# Main.net
KiCad netlist of a schematic drawn in Altium Designer
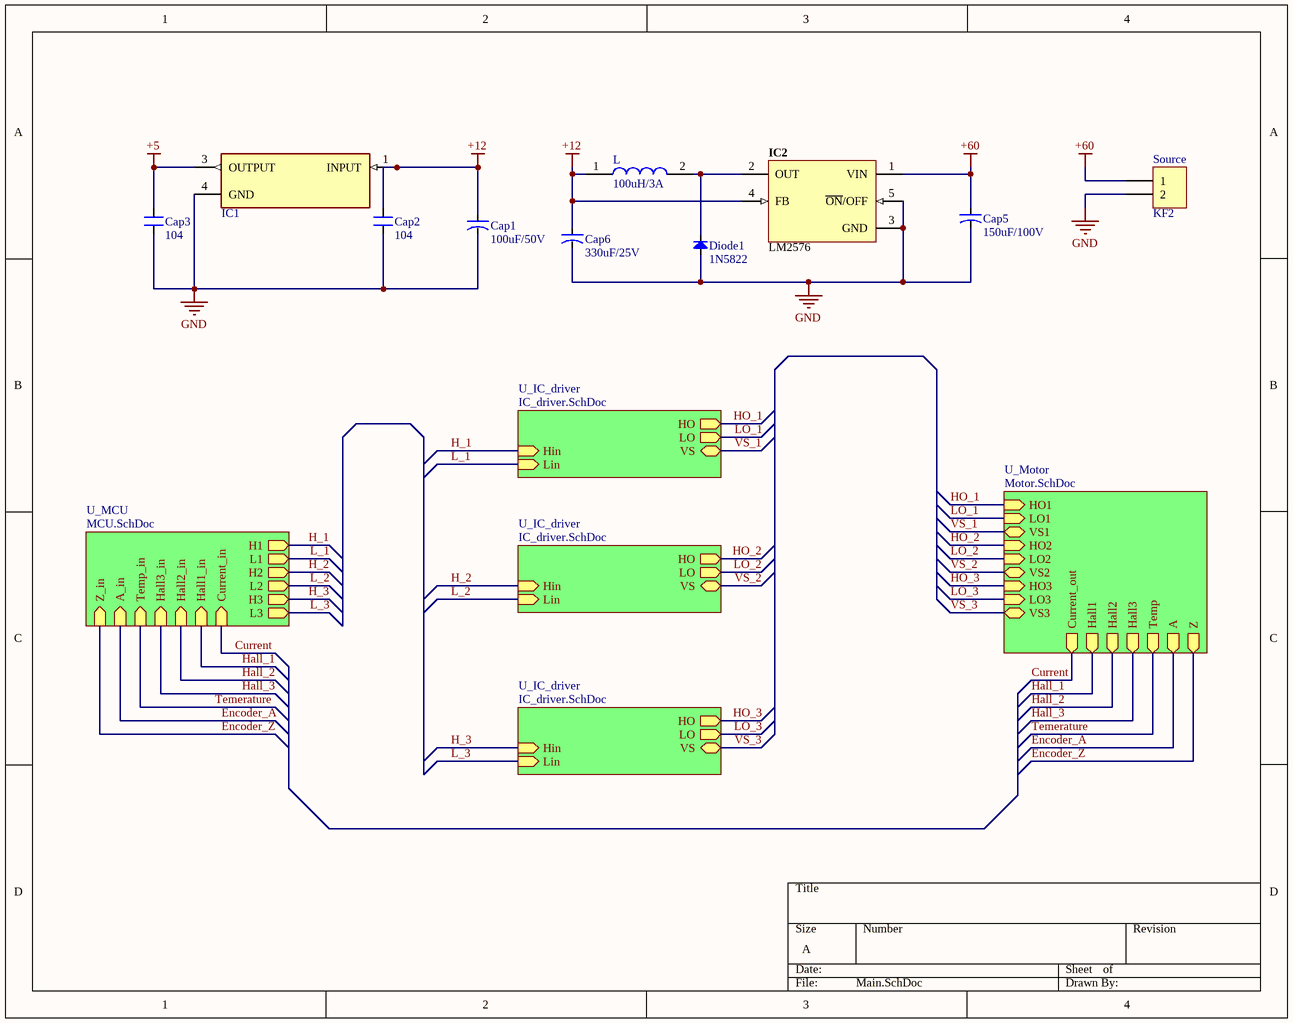
[diagram p0: Main.SchDoc]

(export (version "E")
  (design (tool "Eeschema 10.0.6"))
  (components
    (comp (ref "Cap1")
      (value "100uF/50V")
      (footprint "CAP FILM 1206")
      (description "Polarized Capacitor (Axial)")
      (fields (field (name "PUBLISHER") "Altium Limited"))
      (libsource (lib "LIBRARYALT") (part "CN-ALU-SMD"))
    )
    (comp (ref "Cap2")
      (value "104")
      (footprint "CAP FILM 0603_1608")
      (description "Cap np 104 => 105pF")
      (libsource (lib "echipkool-com-library") (part "CN2"))
    )
    (comp (ref "Cap3")
      (value "104")
      (footprint "CAP FILM 0603_1608")
      (description "Cap np 104 => 105pF")
      (libsource (lib "echipkool-com-library") (part "CN2"))
    )
    (comp (ref "Cap5")
      (value "150uF/100V")
      (footprint "CAP TH ALUM ELEC D10.00mm S5.00mm H20.00mm")
      (description "Polarized Capacitor (Axial)")
      (fields (field (name "PUBLISHER") "Altium Limited"))
      (libsource (lib "LIBRARYALT") (part "CN-ALU-SMD"))
    )
    (comp (ref "Cap6")
      (value "330uF/25V")
      (footprint "CAP-ALU-SMD-F")
      (description "Polarized Capacitor (Axial)")
      (fields (field (name "PUBLISHER") "Altium Limited"))
      (libsource (lib "LIBRARYALT") (part "CN-ALU-SMD"))
    )
    (comp (ref "Diode1")
      (value "1N5822")
      (footprint "DIO-SMD-B")
      (description "Default Diode")
      (fields (field (name "PUBLISHER") "Altium Limited"))
      (libsource (lib "LIBRARYALT") (part "Diode SMD"))
    )
    (comp (ref "IC1")
      (value "L7805CD2T-TR")
      (footprint "STMicroelectronics_D²PAK_0079457_22_MFG")
      (libsource (lib "IC_STMicroelectronics_L7805CD2T-TR_eec") (part "L7805CD2T-TR"))
    )
    (comp (ref "IC2") (value "LM2576") (footprint "TO263") (libsource (lib "LIBRARYALT") (part "LM2596")))
    (comp (ref "L")
      (value "100uH/3A")
      (footprint "SamacSys:INDPM102100X400N")
      (description "Inductor")
      (fields
        (field (name "MANUFACTURER_PART_NUMBER") "CDRH104RNP-680NC")
        (field (name "MOUSER PART NUMBER") "851-CDRH104RNP-680NC")
      )
      (libsource (lib "*") (part "CDRH104RNP-680NC"))
    )
    (comp (ref "Source")
      (value "KF2")
      (footprint "KF2-5.08")
      (fields
        (field (name "MANUFACTURER") "Würth Elektronik eiSos GmbH")
        (field (name "PARTNO") "691103110002")
        (field (name "CREATED BY") "Karrer Zheng")
      )
      (libsource (lib "LIBRARYALT") (part "KF2"))
    )
  )
  (nets
    (net (code "1") (name "+5") (class "Default")
      (node (ref "Cap3") (pin "2") (pinfunction "2_2") (pintype "passive"))
      (node (ref "IC1") (pin "3") (pinfunction "OUTPUT_3") (pintype "output"))
    )
    (net (code "2") (name "+12") (class "Default")
      (node (ref "Cap1") (pin "1") (pinfunction "1_1") (pintype "passive"))
      (node (ref "Cap2") (pin "2") (pinfunction "2_2") (pintype "passive"))
      (node (ref "Cap6") (pin "1") (pinfunction "1_1") (pintype "passive"))
      (node (ref "IC1") (pin "1") (pinfunction "INPUT_1") (pintype "input"))
      (node (ref "IC2") (pin "4") (pinfunction "FB_4") (pintype "input"))
      (node (ref "L") (pin "1") (pinfunction "1_1") (pintype "passive"))
    )
    (net (code "3") (name "+60") (class "Default")
      (node (ref "Cap5") (pin "1") (pinfunction "1_1") (pintype "passive"))
      (node (ref "IC2") (pin "1") (pinfunction "VIN_1") (pintype "power_in"))
      (node (ref "Source") (pin "1") (pinfunction "1_1") (pintype "passive"))
    )
    (net (code "26") (name "GND") (class "Default")
      (node (ref "Cap1") (pin "2") (pinfunction "2_2") (pintype "passive"))
      (node (ref "Cap2") (pin "1") (pinfunction "1_1") (pintype "passive"))
      (node (ref "Cap3") (pin "1") (pinfunction "1_1") (pintype "passive"))
      (node (ref "Cap5") (pin "2") (pinfunction "2_2") (pintype "passive"))
      (node (ref "Cap6") (pin "2") (pinfunction "2_2") (pintype "passive"))
      (node (ref "Diode1") (pin "1") (pinfunction "A_1") (pintype "passive"))
      (node (ref "IC1") (pin "4") (pinfunction "GND_4") (pintype "power_in"))
      (node (ref "IC2") (pin "3") (pinfunction "GND_3") (pintype "power_in"))
      (node (ref "IC2") (pin "5") (pinfunction "~{ON}/OFF_5") (pintype "input"))
      (node (ref "Source") (pin "2") (pinfunction "2_2") (pintype "passive"))
    )
    (net (code "27") (name "Net-(Diode1-K)") (class "Default")
      (node (ref "Diode1") (pin "2") (pinfunction "K_2") (pintype "passive"))
      (node (ref "IC2") (pin "2") (pinfunction "OUT_2") (pintype "power_in"))
      (node (ref "L") (pin "2") (pinfunction "2_2") (pintype "passive"))
    )
  )
)
